# flute.net
KiCad netlist of a schematic drawn in EAGLE
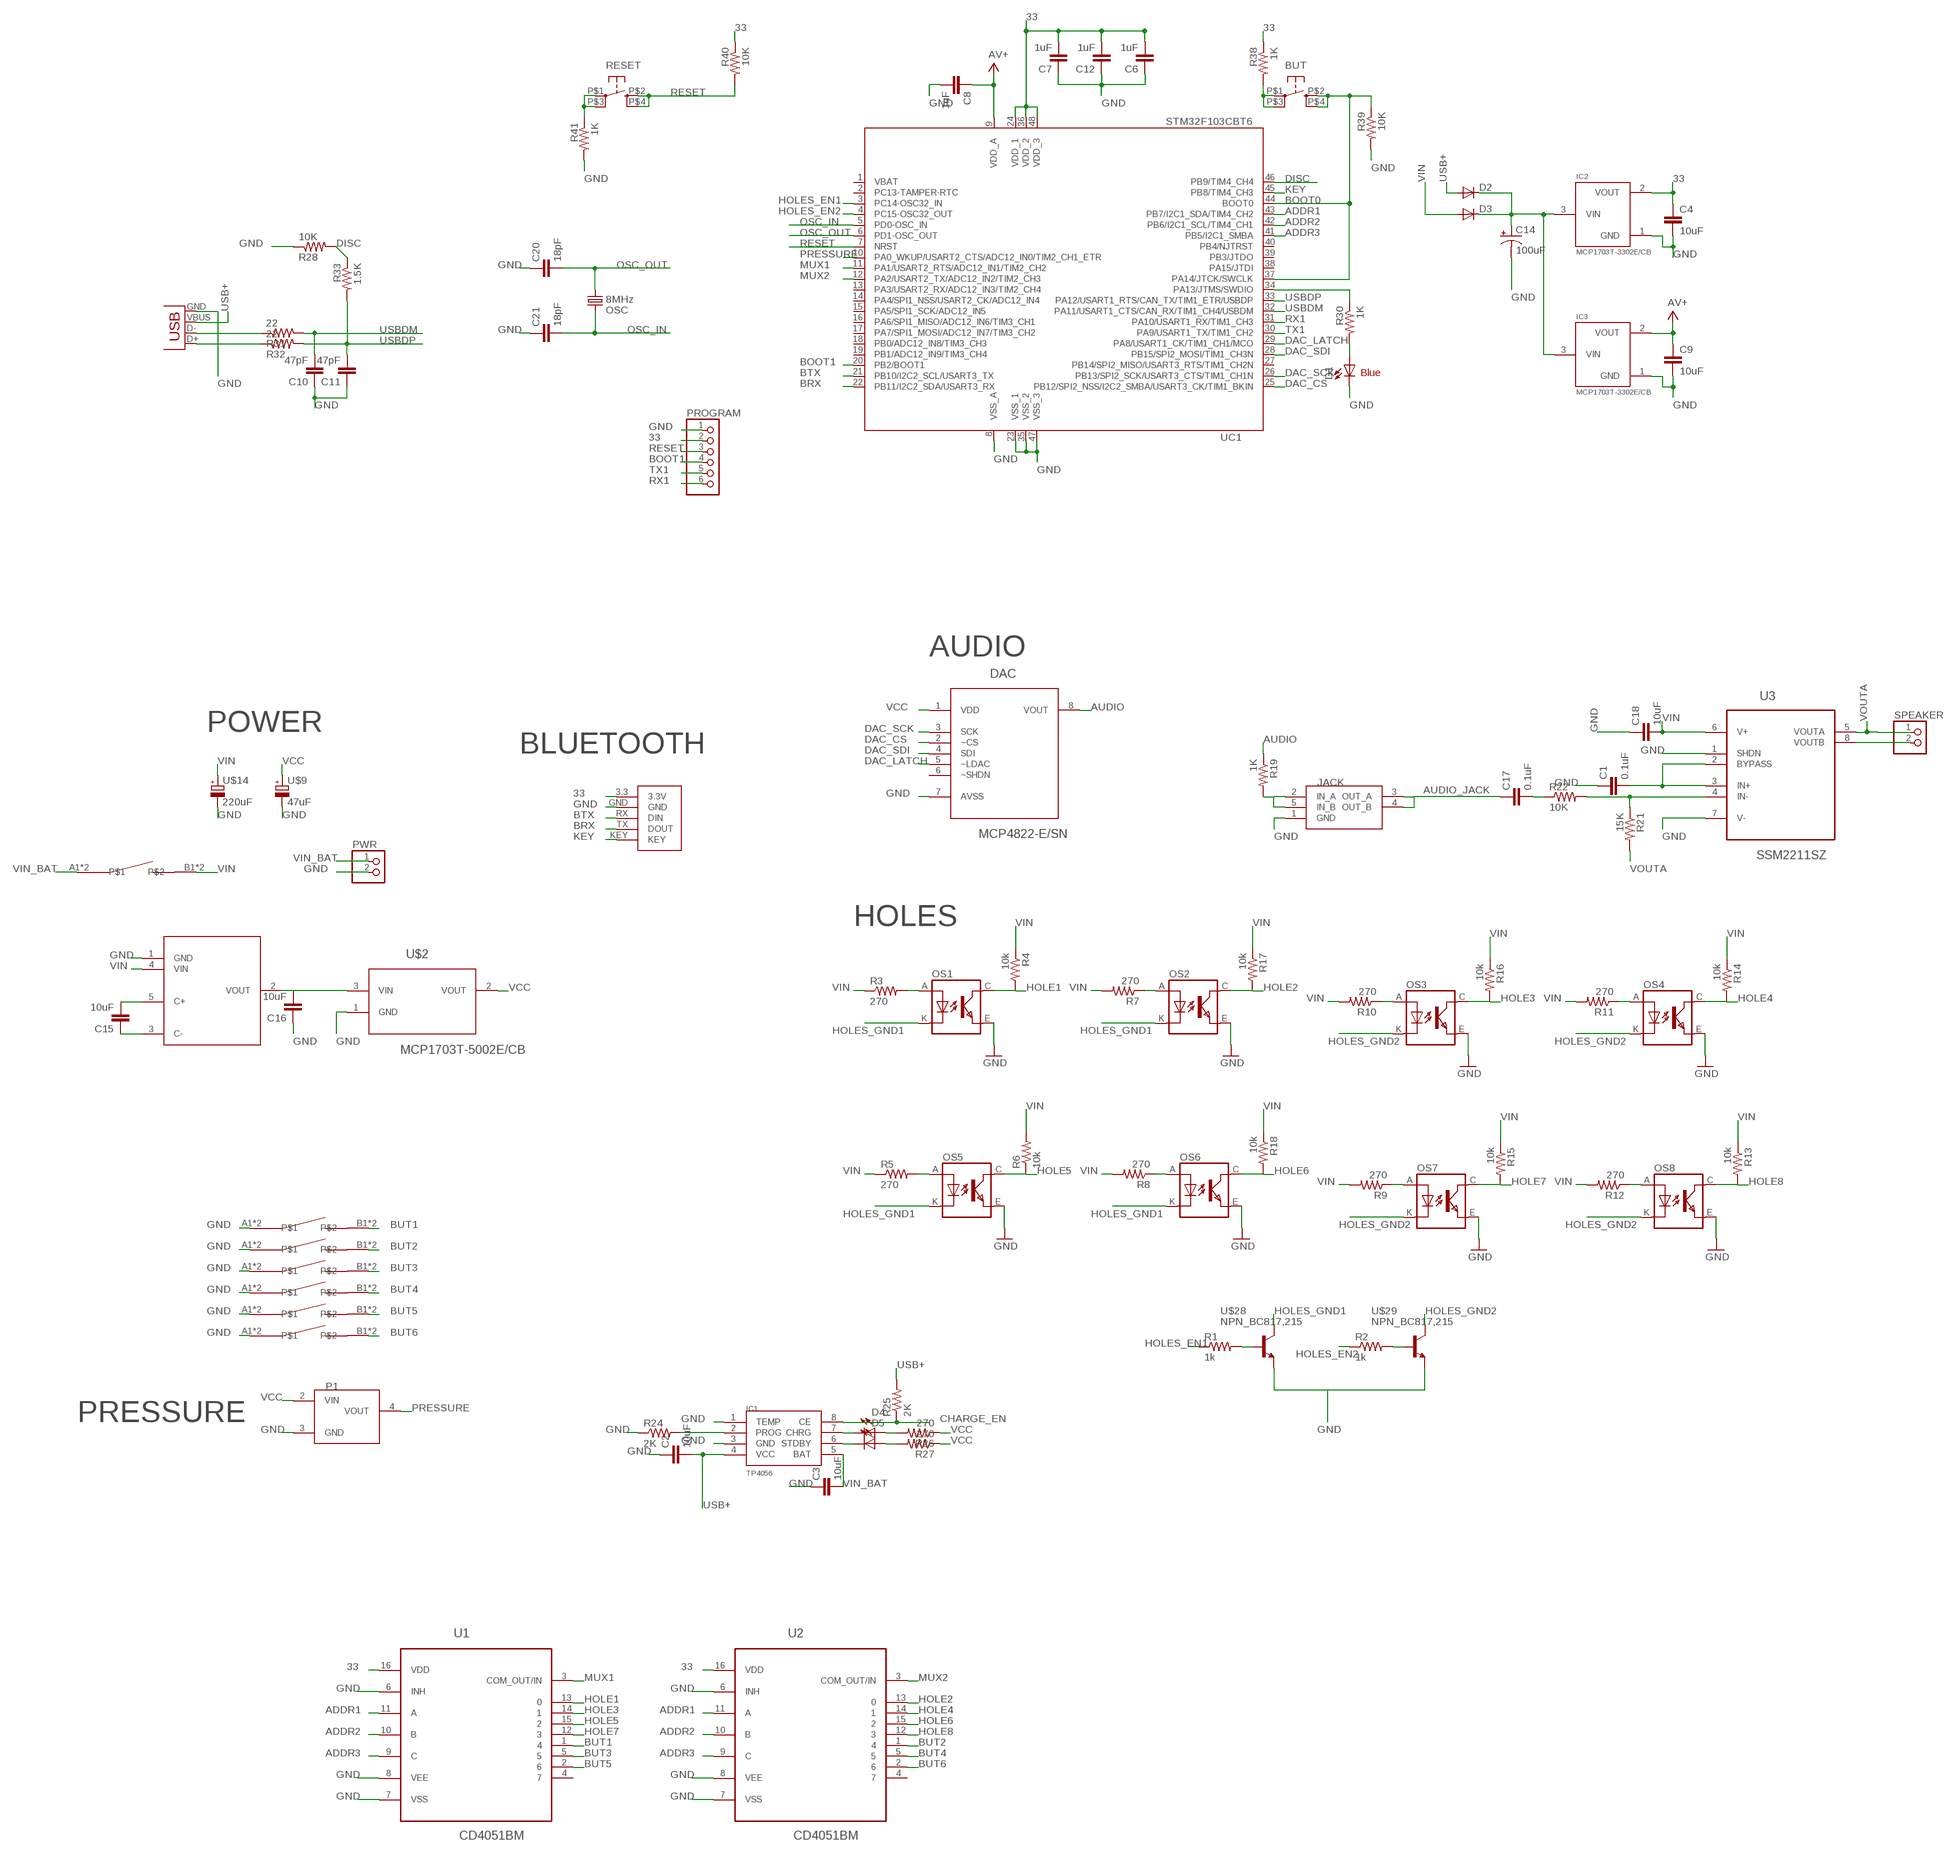
[diagram p0: schematic, sheet 1]

(export (version "E")
  (design (tool "Eeschema 10.0.6"))
  (components
    (comp (ref "BUT")
      (value "KMR211GLFS")
      (footprint "eagle-import:PUSHBUTTON-KMR241GLFS")
      (libsource (lib "eagle-import") (part "BUTTON-KMR241GLFS"))
    )
    (comp (ref "C1")
      (value "0.1uF")
      (footprint "eagle-import:0805")
      (libsource (lib "eagle-import") (part "CAP0805"))
    )
    (comp (ref "C2")
      (value "10uF")
      (footprint "eagle-import:0805")
      (libsource (lib "eagle-import") (part "CAP0805"))
    )
    (comp (ref "C3")
      (value "10uF")
      (footprint "eagle-import:0805")
      (libsource (lib "eagle-import") (part "CAP0805"))
    )
    (comp (ref "C4")
      (value "10uF")
      (footprint "eagle-import:0805")
      (libsource (lib "eagle-import") (part "SparkFun2_CAP0805"))
    )
    (comp (ref "C6")
      (value "1uF")
      (footprint "eagle-import:0805")
      (libsource (lib "eagle-import") (part "CAP0805"))
    )
    (comp (ref "C7")
      (value "1uF")
      (footprint "eagle-import:0805")
      (libsource (lib "eagle-import") (part "CAP0805"))
    )
    (comp (ref "C8")
      (value "1uF")
      (footprint "eagle-import:0805")
      (libsource (lib "eagle-import") (part "CAP0805"))
    )
    (comp (ref "C9")
      (value "10uF")
      (footprint "eagle-import:0805")
      (libsource (lib "eagle-import") (part "SparkFun2_CAP0805"))
    )
    (comp (ref "C10")
      (value "47pF")
      (footprint "eagle-import:0805")
      (libsource (lib "eagle-import") (part "CAP0805"))
    )
    (comp (ref "C11")
      (value "47pF")
      (footprint "eagle-import:0805")
      (libsource (lib "eagle-import") (part "CAP0805"))
    )
    (comp (ref "C12")
      (value "1uF")
      (footprint "eagle-import:0805")
      (libsource (lib "eagle-import") (part "CAP0805"))
    )
    (comp (ref "C14")
      (value "100uF")
      (footprint "eagle-import:EIA3216")
      (libsource (lib "eagle-import") (part "CAP_POL1206"))
    )
    (comp (ref "C15")
      (value "10uF")
      (footprint "eagle-import:0805")
      (libsource (lib "eagle-import") (part "CAP0805"))
    )
    (comp (ref "C16")
      (value "10uF")
      (footprint "eagle-import:0805")
      (libsource (lib "eagle-import") (part "CAP0805"))
    )
    (comp (ref "C17")
      (value "0.1uF")
      (footprint "eagle-import:0805")
      (libsource (lib "eagle-import") (part "CAP0805"))
    )
    (comp (ref "C18")
      (value "10uF")
      (footprint "eagle-import:0805")
      (libsource (lib "eagle-import") (part "CAP0805"))
    )
    (comp (ref "C20")
      (value "18pF")
      (footprint "eagle-import:0805")
      (libsource (lib "eagle-import") (part "CAP0805"))
    )
    (comp (ref "C21")
      (value "18pF")
      (footprint "eagle-import:0805")
      (libsource (lib "eagle-import") (part "CAP0805"))
    )
    (comp (ref "D1")
      (value "Blue")
      (footprint "eagle-import:LED-1206")
      (libsource (lib "eagle-import") (part "LED1206"))
    )
    (comp (ref "D2")
      (value "DIODESOD")
      (footprint "eagle-import:SOD-323")
      (libsource (lib "eagle-import") (part "DIODESOD"))
    )
    (comp (ref "D3")
      (value "DIODESOD")
      (footprint "eagle-import:SOD-323")
      (libsource (lib "eagle-import") (part "DIODESOD"))
    )
    (comp (ref "D4")
      (value "Red")
      (footprint "eagle-import:LED-1206")
      (libsource (lib "eagle-import") (part "LED1206"))
    )
    (comp (ref "D5")
      (value "Green")
      (footprint "eagle-import:LED-1206")
      (libsource (lib "eagle-import") (part "LED1206"))
    )
    (comp (ref "DAC")
      (value "MCP4822-E/SN")
      (footprint "eagle-import:SOIC8-N_MC")
      (libsource (lib "eagle-import") (part "MCP4822-E/SN"))
    )
    (comp (ref "IC1")
      (value "TP4056")
      (footprint "eagle-import:SOP-8")
      (libsource (lib "eagle-import") (part "TP4056"))
    )
    (comp (ref "IC2")
      (value "MCP1703T-3302E/CB")
      (footprint "eagle-import:SOT23")
      (libsource (lib "eagle-import") (part "MCP1700T"))
    )
    (comp (ref "IC3")
      (value "MCP1703T-3302E/CB")
      (footprint "eagle-import:SOT23")
      (libsource (lib "eagle-import") (part "MCP1700T"))
    )
    (comp (ref "JACK")
      (value "JACK")
      (footprint "eagle-import:3F07")
      (libsource (lib "eagle-import") (part "JACK"))
    )
    (comp (ref "OS1")
      (value "TCRT5000")
      (footprint "eagle-import:TCRT5000")
      (libsource (lib "eagle-import") (part "TCRT5000"))
    )
    (comp (ref "OS2")
      (value "TCRT5000")
      (footprint "eagle-import:TCRT5000")
      (libsource (lib "eagle-import") (part "TCRT5000"))
    )
    (comp (ref "OS3")
      (value "TCRT5000")
      (footprint "eagle-import:TCRT5000")
      (libsource (lib "eagle-import") (part "TCRT5000"))
    )
    (comp (ref "OS4")
      (value "TCRT5000")
      (footprint "eagle-import:TCRT5000")
      (libsource (lib "eagle-import") (part "TCRT5000"))
    )
    (comp (ref "OS5")
      (value "TCRT5000")
      (footprint "eagle-import:TCRT5000")
      (libsource (lib "eagle-import") (part "TCRT5000"))
    )
    (comp (ref "OS6")
      (value "TCRT5000")
      (footprint "eagle-import:TCRT5000")
      (libsource (lib "eagle-import") (part "TCRT5000"))
    )
    (comp (ref "OS7")
      (value "TCRT5000")
      (footprint "eagle-import:TCRT5000")
      (libsource (lib "eagle-import") (part "TCRT5000"))
    )
    (comp (ref "OS8")
      (value "TCRT5000")
      (footprint "eagle-import:TCRT5000")
      (libsource (lib "eagle-import") (part "TCRT5000"))
    )
    (comp (ref "OSC")
      (value "8MHz")
      (footprint "eagle-import:CRYSTAL-SMD-5X3")
      (libsource (lib "eagle-import") (part "CRYSTAL5X3"))
    )
    (comp (ref "P1")
      (value "PRESSURE_SENSOR")
      (footprint "eagle-import:MPXV5050GP")
      (libsource (lib "eagle-import") (part "PRESSURE_SENSOR"))
    )
    (comp (ref "PROGRAM")
      (value "CONNEC_1X066PADS")
      (footprint "eagle-import:6PADS")
      (libsource (lib "eagle-import") (part "CONNEC_1X066PADS"))
    )
    (comp (ref "PWR")
      (value "CONNEC_1X02BASIC")
      (footprint "eagle-import:CONNEC_1X02")
      (libsource (lib "eagle-import") (part "CONNEC_1X02BASIC"))
    )
    (comp (ref "R1")
      (value "1k")
      (footprint "eagle-import:0805")
      (libsource (lib "eagle-import") (part "RESISTOR0805-RES"))
    )
    (comp (ref "R2")
      (value "1k")
      (footprint "eagle-import:0805")
      (libsource (lib "eagle-import") (part "RESISTOR0805-RES"))
    )
    (comp (ref "R3")
      (value "270")
      (footprint "eagle-import:0805")
      (libsource (lib "eagle-import") (part "RESISTOR0805-RES"))
    )
    (comp (ref "R4")
      (value "10k")
      (footprint "eagle-import:0805")
      (libsource (lib "eagle-import") (part "RESISTOR0805-RES"))
    )
    (comp (ref "R5")
      (value "270")
      (footprint "eagle-import:0805")
      (libsource (lib "eagle-import") (part "RESISTOR0805-RES"))
    )
    (comp (ref "R6")
      (value "10k")
      (footprint "eagle-import:0805")
      (libsource (lib "eagle-import") (part "RESISTOR0805-RES"))
    )
    (comp (ref "R7")
      (value "270")
      (footprint "eagle-import:0805")
      (libsource (lib "eagle-import") (part "RESISTOR0805-RES"))
    )
    (comp (ref "R8")
      (value "270")
      (footprint "eagle-import:0805")
      (libsource (lib "eagle-import") (part "RESISTOR0805-RES"))
    )
    (comp (ref "R9")
      (value "270")
      (footprint "eagle-import:0805")
      (libsource (lib "eagle-import") (part "RESISTOR0805-RES"))
    )
    (comp (ref "R10")
      (value "270")
      (footprint "eagle-import:0805")
      (libsource (lib "eagle-import") (part "RESISTOR0805-RES"))
    )
    (comp (ref "R11")
      (value "270")
      (footprint "eagle-import:0805")
      (libsource (lib "eagle-import") (part "RESISTOR0805-RES"))
    )
    (comp (ref "R12")
      (value "270")
      (footprint "eagle-import:0805")
      (libsource (lib "eagle-import") (part "RESISTOR0805-RES"))
    )
    (comp (ref "R13")
      (value "10k")
      (footprint "eagle-import:0805")
      (libsource (lib "eagle-import") (part "RESISTOR0805-RES"))
    )
    (comp (ref "R14")
      (value "10k")
      (footprint "eagle-import:0805")
      (libsource (lib "eagle-import") (part "RESISTOR0805-RES"))
    )
    (comp (ref "R15")
      (value "10k")
      (footprint "eagle-import:0805")
      (libsource (lib "eagle-import") (part "RESISTOR0805-RES"))
    )
    (comp (ref "R16")
      (value "10k")
      (footprint "eagle-import:0805")
      (libsource (lib "eagle-import") (part "RESISTOR0805-RES"))
    )
    (comp (ref "R17")
      (value "10k")
      (footprint "eagle-import:0805")
      (libsource (lib "eagle-import") (part "RESISTOR0805-RES"))
    )
    (comp (ref "R18")
      (value "10k")
      (footprint "eagle-import:0805")
      (libsource (lib "eagle-import") (part "RESISTOR0805-RES"))
    )
    (comp (ref "R19")
      (value "1K")
      (footprint "eagle-import:0805")
      (libsource (lib "eagle-import") (part "RESISTOR0805-RES"))
    )
    (comp (ref "R21")
      (value "15K")
      (footprint "eagle-import:0805")
      (libsource (lib "eagle-import") (part "RESISTOR0805-RES"))
    )
    (comp (ref "R22")
      (value "10K")
      (footprint "eagle-import:0805")
      (libsource (lib "eagle-import") (part "RESISTOR0805-RES"))
    )
    (comp (ref "R24")
      (value "2K")
      (footprint "eagle-import:0805")
      (libsource (lib "eagle-import") (part "RESISTOR0805-RES"))
    )
    (comp (ref "R25")
      (value "2K")
      (footprint "eagle-import:0805")
      (libsource (lib "eagle-import") (part "RESISTOR0805-RES"))
    )
    (comp (ref "R26")
      (value "270")
      (footprint "eagle-import:0805")
      (libsource (lib "eagle-import") (part "RESISTOR0805-RES"))
    )
    (comp (ref "R27")
      (value "270")
      (footprint "eagle-import:0805")
      (libsource (lib "eagle-import") (part "RESISTOR0805-RES"))
    )
    (comp (ref "R28")
      (value "10K")
      (footprint "eagle-import:0805")
      (libsource (lib "eagle-import") (part "RESISTOR0805-RES"))
    )
    (comp (ref "R30")
      (value "1K")
      (footprint "eagle-import:0805")
      (libsource (lib "eagle-import") (part "RESISTOR0805-RES"))
    )
    (comp (ref "R31")
      (value "22")
      (footprint "eagle-import:0805")
      (libsource (lib "eagle-import") (part "RESISTOR0805-RES"))
    )
    (comp (ref "R32")
      (value "22")
      (footprint "eagle-import:0805")
      (libsource (lib "eagle-import") (part "RESISTOR0805-RES"))
    )
    (comp (ref "R33")
      (value "1.5K")
      (footprint "eagle-import:0805")
      (libsource (lib "eagle-import") (part "RESISTOR0805-RES"))
    )
    (comp (ref "R38")
      (value "1K")
      (footprint "eagle-import:0805")
      (libsource (lib "eagle-import") (part "RESISTOR0805-RES"))
    )
    (comp (ref "R39")
      (value "10K")
      (footprint "eagle-import:0805")
      (libsource (lib "eagle-import") (part "RESISTOR0805-RES"))
    )
    (comp (ref "R40")
      (value "10K")
      (footprint "eagle-import:0805")
      (libsource (lib "eagle-import") (part "RESISTOR0805-RES"))
    )
    (comp (ref "R41")
      (value "1K")
      (footprint "eagle-import:0805")
      (libsource (lib "eagle-import") (part "RESISTOR0805-RES"))
    )
    (comp (ref "RESET")
      (value "KMR211GLFS")
      (footprint "eagle-import:PUSHBUTTON-KMR241GLFS")
      (libsource (lib "eagle-import") (part "BUTTON-KMR241GLFS"))
    )
    (comp (ref "SPEAKER")
      (value "CONNEC_1X02BASIC")
      (footprint "eagle-import:CONNEC_1X02")
      (libsource (lib "eagle-import") (part "CONNEC_1X02BASIC"))
    )
    (comp (ref "U$1")
      (value "MAX1683")
      (footprint "eagle-import:SOT23-5")
      (libsource (lib "eagle-import") (part "MAX1683"))
    )
    (comp (ref "U$2")
      (value "MCP1703T-5002E/CB")
      (footprint "eagle-import:SOT95P300X145-3N")
      (libsource (lib "eagle-import") (part "MCP1703T-5002E/CB"))
    )
    (comp (ref "U$9")
      (value "47uF")
      (footprint "eagle-import:PANASONIC_D")
      (libsource (lib "eagle-import") (part "CPOL_EUPANASONIC_D"))
    )
    (comp (ref "U$14")
      (value "220uF")
      (footprint "eagle-import:PANASONIC_D8")
      (libsource (lib "eagle-import") (part "CPOL_EUPANASONIC_D8"))
    )
    (comp (ref "U$16")
      (value "SWITCHKCD11")
      (footprint "eagle-import:KCD11")
      (libsource (lib "eagle-import") (part "SWITCHKCD11"))
    )
    (comp (ref "U$18")
      (value "SWITCH6X6X10")
      (footprint "eagle-import:SWITCH_6X6X10")
      (libsource (lib "eagle-import") (part "SWITCH6X6X10"))
    )
    (comp (ref "U$19")
      (value "SWITCH6X6X10")
      (footprint "eagle-import:SWITCH_6X6X10")
      (libsource (lib "eagle-import") (part "SWITCH6X6X10"))
    )
    (comp (ref "U$20")
      (value "SWITCH6X6X10")
      (footprint "eagle-import:SWITCH_6X6X10")
      (libsource (lib "eagle-import") (part "SWITCH6X6X10"))
    )
    (comp (ref "U$21")
      (value "SWITCH6X6X10")
      (footprint "eagle-import:SWITCH_6X6X10")
      (libsource (lib "eagle-import") (part "SWITCH6X6X10"))
    )
    (comp (ref "U$22")
      (value "SWITCH6X6X10")
      (footprint "eagle-import:SWITCH_6X6X10")
      (libsource (lib "eagle-import") (part "SWITCH6X6X10"))
    )
    (comp (ref "U$23")
      (value "SWITCH6X6X10")
      (footprint "eagle-import:SWITCH_6X6X10")
      (libsource (lib "eagle-import") (part "SWITCH6X6X10"))
    )
    (comp (ref "U$24")
      (value "HC05")
      (footprint "eagle-import:HC-05")
      (libsource (lib "eagle-import") (part "HC05"))
    )
    (comp (ref "U$28")
      (value "NPN_BC817,215")
      (footprint "eagle-import:SOT-23")
      (libsource (lib "eagle-import") (part "NPN_BC817,215"))
    )
    (comp (ref "U$29")
      (value "NPN_BC817,215")
      (footprint "eagle-import:SOT-23")
      (libsource (lib "eagle-import") (part "NPN_BC817,215"))
    )
    (comp (ref "U1")
      (value "CD4051BM")
      (footprint "eagle-import:SOIC127P600X175-16N")
      (libsource (lib "eagle-import") (part "CD4051BM"))
    )
    (comp (ref "U2")
      (value "CD4051BM")
      (footprint "eagle-import:SOIC127P600X175-16N")
      (libsource (lib "eagle-import") (part "CD4051BM"))
    )
    (comp (ref "U3")
      (value "SSM2211SZ")
      (footprint "eagle-import:SOIC127P600X175-8N")
      (libsource (lib "eagle-import") (part "SSM2211SZ"))
    )
    (comp (ref "UC1")
      (value "STM32F103CBT6")
      (footprint "eagle-import:LQFP48")
      (libsource (lib "eagle-import") (part "STM32F103CB"))
    )
    (comp (ref "X1")
      (value "USB-MINIB")
      (footprint "eagle-import:USB-MINIB")
      (libsource (lib "eagle-import") (part "USBSMD"))
    )
  )
  (nets
    (net (code "1") (name "/33") (class "Default")
      (node (ref "C12") (pin "2") (pinfunction "2_2") (pintype "passive"))
      (node (ref "C4") (pin "1") (pinfunction "1_1") (pintype "passive"))
      (node (ref "C6") (pin "2") (pinfunction "2_2") (pintype "passive"))
      (node (ref "C7") (pin "2") (pinfunction "2_2") (pintype "passive"))
      (node (ref "IC2") (pin "2") (pinfunction "VOUT_2") (pintype "bidirectional"))
      (node (ref "PROGRAM") (pin "2") (pinfunction "2_2") (pintype "passive"))
      (node (ref "R38") (pin "1") (pinfunction "1_1") (pintype "passive"))
      (node (ref "R40") (pin "1") (pinfunction "1_1") (pintype "passive"))
      (node (ref "U$24") (pin "3.3") (pinfunction "3.3V_3.3") (pintype "bidirectional"))
      (node (ref "U1") (pin "16") (pinfunction "VDD_16") (pintype "input"))
      (node (ref "U2") (pin "16") (pinfunction "VDD_16") (pintype "input"))
      (node (ref "UC1") (pin "24") (pinfunction "VDD_1_24") (pintype "power_in"))
      (node (ref "UC1") (pin "36") (pinfunction "VDD_2_36") (pintype "power_in"))
      (node (ref "UC1") (pin "48") (pinfunction "VDD_3_48") (pintype "power_in"))
    )
    (net (code "2") (name "/ADDR1") (class "Default")
      (node (ref "U1") (pin "11") (pinfunction "A_11") (pintype "input"))
      (node (ref "U2") (pin "11") (pinfunction "A_11") (pintype "input"))
      (node (ref "UC1") (pin "43") (pinfunction "PB7/I2C1_SDA/TIM4_CH2_43") (pintype "bidirectional"))
    )
    (net (code "3") (name "/ADDR2") (class "Default")
      (node (ref "U1") (pin "10") (pinfunction "B_10") (pintype "input"))
      (node (ref "U2") (pin "10") (pinfunction "B_10") (pintype "input"))
      (node (ref "UC1") (pin "42") (pinfunction "PB6/I2C1_SCL/TIM4_CH1_42") (pintype "input"))
    )
    (net (code "4") (name "/ADDR3") (class "Default")
      (node (ref "U1") (pin "9") (pinfunction "C_9") (pintype "bidirectional"))
      (node (ref "U2") (pin "9") (pinfunction "C_9") (pintype "bidirectional"))
      (node (ref "UC1") (pin "41") (pinfunction "PB5/I2C1_SMBA_41") (pintype "input"))
    )
    (net (code "5") (name "/AUDIO") (class "Default")
      (node (ref "DAC") (pin "8") (pinfunction "VOUT_8") (pintype "output"))
      (node (ref "R19") (pin "1") (pinfunction "1_1") (pintype "passive"))
    )
    (net (code "6") (name "/AUDIO_JACK") (class "Default")
      (node (ref "C17") (pin "1") (pinfunction "1_1") (pintype "passive"))
      (node (ref "JACK") (pin "3") (pinfunction "OUT_A_3") (pintype "bidirectional"))
      (node (ref "JACK") (pin "4") (pinfunction "OUT_B_4") (pintype "bidirectional"))
    )
    (net (code "7") (name "/BOOT1") (class "Default")
      (node (ref "PROGRAM") (pin "4") (pinfunction "4_4") (pintype "passive"))
      (node (ref "UC1") (pin "20") (pinfunction "PB2/BOOT1_20") (pintype "bidirectional"))
    )
    (net (code "8") (name "/BRX") (class "Default")
      (node (ref "U$24") (pin "TX") (pinfunction "DOUT_TX") (pintype "bidirectional"))
      (node (ref "UC1") (pin "22") (pinfunction "PB11/I2C2_SDA/USART3_RX_22") (pintype "input"))
    )
    (net (code "9") (name "/BTX") (class "Default")
      (node (ref "U$24") (pin "RX") (pinfunction "DIN_RX") (pintype "bidirectional"))
      (node (ref "UC1") (pin "21") (pinfunction "PB10/I2C2_SCL/USART3_TX_21") (pintype "input"))
    )
    (net (code "10") (name "/BUT1") (class "Default")
      (node (ref "U$18") (pin "B1") (pinfunction "P$2_B1") (pintype "bidirectional"))
      (node (ref "U$18") (pin "B2") (pinfunction "P$2_B2") (pintype "bidirectional"))
      (node (ref "U1") (pin "1") (pinfunction "4_1") (pintype "bidirectional"))
    )
    (net (code "11") (name "/BUT2") (class "Default")
      (node (ref "U$19") (pin "B1") (pinfunction "P$2_B1") (pintype "bidirectional"))
      (node (ref "U$19") (pin "B2") (pinfunction "P$2_B2") (pintype "bidirectional"))
      (node (ref "U2") (pin "1") (pinfunction "4_1") (pintype "bidirectional"))
    )
    (net (code "12") (name "/BUT3") (class "Default")
      (node (ref "U$20") (pin "B1") (pinfunction "P$2_B1") (pintype "bidirectional"))
      (node (ref "U$20") (pin "B2") (pinfunction "P$2_B2") (pintype "bidirectional"))
      (node (ref "U1") (pin "5") (pinfunction "5_5") (pintype "bidirectional"))
    )
    (net (code "13") (name "/BUT4") (class "Default")
      (node (ref "U$21") (pin "B1") (pinfunction "P$2_B1") (pintype "bidirectional"))
      (node (ref "U$21") (pin "B2") (pinfunction "P$2_B2") (pintype "bidirectional"))
      (node (ref "U2") (pin "5") (pinfunction "5_5") (pintype "bidirectional"))
    )
    (net (code "14") (name "/BUT5") (class "Default")
      (node (ref "U$22") (pin "B1") (pinfunction "P$2_B1") (pintype "bidirectional"))
      (node (ref "U$22") (pin "B2") (pinfunction "P$2_B2") (pintype "bidirectional"))
      (node (ref "U1") (pin "2") (pinfunction "6_2") (pintype "bidirectional"))
    )
    (net (code "15") (name "/BUT6") (class "Default")
      (node (ref "U$23") (pin "B1") (pinfunction "P$2_B1") (pintype "bidirectional"))
      (node (ref "U$23") (pin "B2") (pinfunction "P$2_B2") (pintype "bidirectional"))
      (node (ref "U2") (pin "2") (pinfunction "6_2") (pintype "bidirectional"))
    )
    (net (code "16") (name "/CHARGE_EN") (class "Default")
      (node (ref "IC1") (pin "8") (pinfunction "CE_8") (pintype "bidirectional"))
      (node (ref "R25") (pin "1") (pinfunction "1_1") (pintype "passive"))
    )
    (net (code "17") (name "/DAC_CS") (class "Default")
      (node (ref "DAC") (pin "2") (pinfunction "~{CS}_2") (pintype "input"))
      (node (ref "UC1") (pin "25") (pinfunction "PB12/SPI2_NSS/I2C2_SMBA/USART3_CK/TIM1_BKIN_25") (pintype "input"))
    )
    (net (code "18") (name "/DAC_LATCH") (class "Default")
      (node (ref "DAC") (pin "5") (pinfunction "~{LDAC}_5") (pintype "input"))
      (node (ref "UC1") (pin "29") (pinfunction "PA8/USART1_CK/TIM1_CH1/MCO_29") (pintype "bidirectional"))
    )
    (net (code "19") (name "/DAC_SCK") (class "Default")
      (node (ref "DAC") (pin "3") (pinfunction "SCK_3") (pintype "input"))
      (node (ref "UC1") (pin "26") (pinfunction "PB13/SPI2_SCK/USART3_CTS/TIM1_CH1N_26") (pintype "input"))
    )
    (net (code "20") (name "/DAC_SDI") (class "Default")
      (node (ref "DAC") (pin "4") (pinfunction "SDI_4") (pintype "input"))
      (node (ref "UC1") (pin "28") (pinfunction "PB15/SPI2_MOSI/TIM1_CH3N_28") (pintype "input"))
    )
    (net (code "21") (name "/DISC") (class "Default")
      (node (ref "R28") (pin "2") (pinfunction "2_2") (pintype "passive"))
      (node (ref "R33") (pin "1") (pinfunction "1_1") (pintype "passive"))
      (node (ref "UC1") (pin "46") (pinfunction "PB9/TIM4_CH4_46") (pintype "input"))
    )
    (net (code "22") (name "/HOLE1") (class "Default")
      (node (ref "OS1") (pin "C") (pinfunction "COLLECTOR_C") (pintype "passive"))
      (node (ref "R4") (pin "2") (pinfunction "2_2") (pintype "passive"))
      (node (ref "U1") (pin "13") (pinfunction "0_13") (pintype "bidirectional"))
    )
    (net (code "23") (name "/HOLE2") (class "Default")
      (node (ref "OS2") (pin "C") (pinfunction "COLLECTOR_C") (pintype "passive"))
      (node (ref "R17") (pin "2") (pinfunction "2_2") (pintype "passive"))
      (node (ref "U2") (pin "13") (pinfunction "0_13") (pintype "bidirectional"))
    )
    (net (code "24") (name "/HOLE3") (class "Default")
      (node (ref "OS3") (pin "C") (pinfunction "COLLECTOR_C") (pintype "passive"))
      (node (ref "R16") (pin "2") (pinfunction "2_2") (pintype "passive"))
      (node (ref "U1") (pin "14") (pinfunction "1_14") (pintype "bidirectional"))
    )
    (net (code "25") (name "/HOLE4") (class "Default")
      (node (ref "OS4") (pin "C") (pinfunction "COLLECTOR_C") (pintype "passive"))
      (node (ref "R14") (pin "2") (pinfunction "2_2") (pintype "passive"))
      (node (ref "U2") (pin "14") (pinfunction "1_14") (pintype "bidirectional"))
    )
    (net (code "26") (name "/HOLE5") (class "Default")
      (node (ref "OS5") (pin "C") (pinfunction "COLLECTOR_C") (pintype "passive"))
      (node (ref "R6") (pin "1") (pinfunction "1_1") (pintype "passive"))
      (node (ref "U1") (pin "15") (pinfunction "2_15") (pintype "bidirectional"))
    )
    (net (code "27") (name "/HOLE6") (class "Default")
      (node (ref "OS6") (pin "C") (pinfunction "COLLECTOR_C") (pintype "passive"))
      (node (ref "R18") (pin "2") (pinfunction "2_2") (pintype "passive"))
      (node (ref "U2") (pin "15") (pinfunction "2_15") (pintype "bidirectional"))
    )
    (net (code "28") (name "/HOLE7") (class "Default")
      (node (ref "OS7") (pin "C") (pinfunction "COLLECTOR_C") (pintype "passive"))
      (node (ref "R15") (pin "2") (pinfunction "2_2") (pintype "passive"))
      (node (ref "U1") (pin "12") (pinfunction "3_12") (pintype "bidirectional"))
    )
    (net (code "29") (name "/HOLE8") (class "Default")
      (node (ref "OS8") (pin "C") (pinfunction "COLLECTOR_C") (pintype "passive"))
      (node (ref "R13") (pin "2") (pinfunction "2_2") (pintype "passive"))
      (node (ref "U2") (pin "12") (pinfunction "3_12") (pintype "bidirectional"))
    )
    (net (code "30") (name "/HOLES_EN1") (class "Default")
      (node (ref "R1") (pin "1") (pinfunction "1_1") (pintype "passive"))
      (node (ref "UC1") (pin "3") (pinfunction "PC14-OSC32_IN_3") (pintype "input"))
    )
    (net (code "31") (name "/HOLES_EN2") (class "Default")
      (node (ref "R2") (pin "1") (pinfunction "1_1") (pintype "passive"))
      (node (ref "UC1") (pin "4") (pinfunction "PC15-OSC32_OUT_4") (pintype "input"))
    )
    (net (code "32") (name "/HOLES_GND1") (class "Default")
      (node (ref "OS1") (pin "K") (pinfunction "CATHODE_K") (pintype "passive"))
      (node (ref "OS2") (pin "K") (pinfunction "CATHODE_K") (pintype "passive"))
      (node (ref "OS5") (pin "K") (pinfunction "CATHODE_K") (pintype "passive"))
      (node (ref "OS6") (pin "K") (pinfunction "CATHODE_K") (pintype "passive"))
      (node (ref "U$28") (pin "3") (pinfunction "C_3") (pintype "passive"))
    )
    (net (code "33") (name "/HOLES_GND2") (class "Default")
      (node (ref "OS3") (pin "K") (pinfunction "CATHODE_K") (pintype "passive"))
      (node (ref "OS4") (pin "K") (pinfunction "CATHODE_K") (pintype "passive"))
      (node (ref "OS7") (pin "K") (pinfunction "CATHODE_K") (pintype "passive"))
      (node (ref "OS8") (pin "K") (pinfunction "CATHODE_K") (pintype "passive"))
      (node (ref "U$29") (pin "3") (pinfunction "C_3") (pintype "passive"))
    )
    (net (code "34") (name "/KEY") (class "Default")
      (node (ref "U$24") (pin "KEY") (pinfunction "KEY_KEY") (pintype "bidirectional"))
      (node (ref "UC1") (pin "45") (pinfunction "PB8/TIM4_CH3_45") (pintype "bidirectional"))
    )
    (net (code "35") (name "/MUX1") (class "Default")
      (node (ref "U1") (pin "3") (pinfunction "COM_OUT/IN_3") (pintype "bidirectional"))
      (node (ref "UC1") (pin "11") (pinfunction "PA1/USART2_RTS/ADC12_IN1/TIM2_CH2_11") (pintype "bidirectional"))
    )
    (net (code "36") (name "/MUX2") (class "Default")
      (node (ref "U2") (pin "3") (pinfunction "COM_OUT/IN_3") (pintype "bidirectional"))
      (node (ref "UC1") (pin "12") (pinfunction "PA2/USART2_TX/ADC12_IN2/TIM2_CH3_12") (pintype "bidirectional"))
    )
    (net (code "37") (name "/OSC_IN") (class "Default")
      (node (ref "C21") (pin "2") (pinfunction "2_2") (pintype "passive"))
      (node (ref "OSC") (pin "3") (pinfunction "2_3") (pintype "passive"))
      (node (ref "UC1") (pin "5") (pinfunction "PD0-OSC_IN_5") (pintype "input"))
    )
    (net (code "38") (name "/OSC_OUT") (class "Default")
      (node (ref "C20") (pin "2") (pinfunction "2_2") (pintype "passive"))
      (node (ref "OSC") (pin "1") (pinfunction "1_1") (pintype "passive"))
      (node (ref "UC1") (pin "6") (pinfunction "PD1-OSC_OUT_6") (pintype "input"))
    )
    (net (code "39") (name "/PRESSURE") (class "Default")
      (node (ref "P1") (pin "4") (pinfunction "VOUT_4") (pintype "bidirectional"))
      (node (ref "UC1") (pin "10") (pinfunction "PA0_WKUP/USART2_CTS/ADC12_IN0/TIM2_CH1_ETR_10") (pintype "bidirectional"))
    )
    (net (code "40") (name "/RESET") (class "Default")
      (node (ref "PROGRAM") (pin "3") (pinfunction "3_3") (pintype "passive"))
      (node (ref "R40") (pin "2") (pinfunction "2_2") (pintype "passive"))
      (node (ref "RESET") (pin "P$2") (pinfunction "2_P$2") (pintype "passive"))
      (node (ref "RESET") (pin "P$4") (pinfunction "4_P$4") (pintype "passive"))
      (node (ref "UC1") (pin "7") (pinfunction "NRST_7") (pintype "input"))
    )
    (net (code "41") (name "/RX1") (class "Default")
      (node (ref "PROGRAM") (pin "6") (pinfunction "6_6") (pintype "passive"))
      (node (ref "UC1") (pin "31") (pinfunction "PA10/USART1_RX/TIM1_CH3_31") (pintype "bidirectional"))
    )
    (net (code "42") (name "/TX1") (class "Default")
      (node (ref "PROGRAM") (pin "5") (pinfunction "5_5") (pintype "passive"))
      (node (ref "UC1") (pin "30") (pinfunction "PA9/USART1_TX/TIM1_CH2_30") (pintype "input"))
    )
    (net (code "43") (name "/USB+") (class "Default")
      (node (ref "C2") (pin "2") (pinfunction "2_2") (pintype "passive"))
      (node (ref "D2") (pin "2") (pinfunction "A_2") (pintype "passive"))
      (node (ref "IC1") (pin "4") (pinfunction "VCC_4") (pintype "bidirectional"))
      (node (ref "R25") (pin "2") (pinfunction "2_2") (pintype "passive"))
      (node (ref "X1") (pin "VBUS") (pinfunction "VBUS_VBUS") (pintype "bidirectional"))
    )
    (net (code "44") (name "/USBDM") (class "Default")
      (node (ref "C10") (pin "2") (pinfunction "2_2") (pintype "passive"))
      (node (ref "R31") (pin "2") (pinfunction "2_2") (pintype "passive"))
      (node (ref "UC1") (pin "32") (pinfunction "PA11/USART1_CTS/CAN_RX/TIM1_CH4/USBDM_32") (pintype "bidirectional"))
    )
    (net (code "45") (name "/USBDP") (class "Default")
      (node (ref "C11") (pin "2") (pinfunction "2_2") (pintype "passive"))
      (node (ref "R32") (pin "2") (pinfunction "2_2") (pintype "passive"))
      (node (ref "R33") (pin "2") (pinfunction "2_2") (pintype "passive"))
      (node (ref "UC1") (pin "33") (pinfunction "PA12/USART1_RTS/CAN_TX/TIM1_ETR/USBDP_33") (pintype "bidirectional"))
    )
    (net (code "46") (name "/VBAT") (class "Default")
      (node (ref "UC1") (pin "1") (pinfunction "VBAT_1") (pintype "power_in"))
    )
    (net (code "47") (name "/VCC") (class "Default")
      (node (ref "DAC") (pin "1") (pinfunction "VDD_1") (pintype "power_in"))
      (node (ref "P1") (pin "2") (pinfunction "VIN_2") (pintype "bidirectional"))
      (node (ref "R26") (pin "1") (pinfunction "1_1") (pintype "passive"))
      (node (ref "R27") (pin "1") (pinfunction "1_1") (pintype "passive"))
      (node (ref "U$2") (pin "2") (pinfunction "VOUT_2") (pintype "output"))
      (node (ref "U$9") (pin "+") (pinfunction "+_+") (pintype "passive"))
    )
    (net (code "48") (name "/VIN") (class "Default")
      (node (ref "C18") (pin "2") (pinfunction "2_2") (pintype "passive"))
      (node (ref "D3") (pin "2") (pinfunction "A_2") (pintype "passive"))
      (node (ref "R10") (pin "2") (pinfunction "2_2") (pintype "passive"))
      (node (ref "R11") (pin "2") (pinfunction "2_2") (pintype "passive"))
      (node (ref "R12") (pin "2") (pinfunction "2_2") (pintype "passive"))
      (node (ref "R13") (pin "1") (pinfunction "1_1") (pintype "passive"))
      (node (ref "R14") (pin "1") (pinfunction "1_1") (pintype "passive"))
      (node (ref "R15") (pin "1") (pinfunction "1_1") (pintype "passive"))
      (node (ref "R16") (pin "1") (pinfunction "1_1") (pintype "passive"))
      (node (ref "R17") (pin "1") (pinfunction "1_1") (pintype "passive"))
      (node (ref "R18") (pin "1") (pinfunction "1_1") (pintype "passive"))
      (node (ref "R3") (pin "1") (pinfunction "1_1") (pintype "passive"))
      (node (ref "R4") (pin "1") (pinfunction "1_1") (pintype "passive"))
      (node (ref "R5") (pin "1") (pinfunction "1_1") (pintype "passive"))
      (node (ref "R6") (pin "2") (pinfunction "2_2") (pintype "passive"))
      (node (ref "R7") (pin "2") (pinfunction "2_2") (pintype "passive"))
      (node (ref "R8") (pin "2") (pinfunction "2_2") (pintype "passive"))
      (node (ref "R9") (pin "2") (pinfunction "2_2") (pintype "passive"))
      (node (ref "U$1") (pin "4") (pinfunction "VIN_4") (pintype "bidirectional"))
      (node (ref "U$14") (pin "+") (pinfunction "+_+") (pintype "passive"))
      (node (ref "U$16") (pin "B1") (pinfunction "P$2_B1") (pintype "bidirectional"))
      (node (ref "U$16") (pin "B2") (pinfunction "P$2_B2") (pintype "bidirectional"))
      (node (ref "U3") (pin "6") (pinfunction "V+_6") (pintype "power_in"))
    )
    (net (code "49") (name "/VIN_BAT") (class "Default")
      (node (ref "C3") (pin "2") (pinfunction "2_2") (pintype "passive"))
      (node (ref "IC1") (pin "5") (pinfunction "BAT_5") (pintype "bidirectional"))
      (node (ref "PWR") (pin "1") (pinfunction "1_1") (pintype "passive"))
      (node (ref "U$16") (pin "A1") (pinfunction "P$1_A1") (pintype "bidirectional"))
      (node (ref "U$16") (pin "A2") (pinfunction "P$1_A2") (pintype "bidirectional"))
    )
    (net (code "50") (name "/VOUTA") (class "Default")
      (node (ref "R21") (pin "2") (pinfunction "2_2") (pintype "passive"))
      (node (ref "SPEAKER") (pin "1") (pinfunction "1_1") (pintype "passive"))
      (node (ref "U3") (pin "5") (pinfunction "VOUTA_5") (pintype "output"))
    )
    (net (code "51") (name "AV+") (class "Default")
      (node (ref "C8") (pin "1") (pinfunction "1_1") (pintype "passive"))
      (node (ref "C9") (pin "1") (pinfunction "1_1") (pintype "passive"))
      (node (ref "IC3") (pin "2") (pinfunction "VOUT_2") (pintype "bidirectional"))
      (node (ref "UC1") (pin "9") (pinfunction "VDD_A_9") (pintype "power_in"))
    )
    (net (code "52") (name "GND") (class "Default")
      (node (ref "C1") (pin "1") (pinfunction "1_1") (pintype "passive"))
      (node (ref "C10") (pin "1") (pinfunction "1_1") (pintype "passive"))
      (node (ref "C11") (pin "1") (pinfunction "1_1") (pintype "passive"))
      (node (ref "C12") (pin "1") (pinfunction "1_1") (pintype "passive"))
      (node (ref "C14") (pin "C") (pinfunction "-_C") (pintype "passive"))
      (node (ref "C16") (pin "1") (pinfunction "1_1") (pintype "passive"))
      (node (ref "C18") (pin "1") (pinfunction "1_1") (pintype "passive"))
      (node (ref "C2") (pin "1") (pinfunction "1_1") (pintype "passive"))
      (node (ref "C20") (pin "1") (pinfunction "1_1") (pintype "passive"))
      (node (ref "C21") (pin "1") (pinfunction "1_1") (pintype "passive"))
      (node (ref "C3") (pin "1") (pinfunction "1_1") (pintype "passive"))
      (node (ref "C4") (pin "2") (pinfunction "2_2") (pintype "passive"))
      (node (ref "C6") (pin "1") (pinfunction "1_1") (pintype "passive"))
      (node (ref "C7") (pin "1") (pinfunction "1_1") (pintype "passive"))
      (node (ref "C8") (pin "2") (pinfunction "2_2") (pintype "passive"))
      (node (ref "C9") (pin "2") (pinfunction "2_2") (pintype "passive"))
      (node (ref "D1") (pin "C") (pinfunction "C_C") (pintype "passive"))
      (node (ref "DAC") (pin "7") (pinfunction "AVSS_7") (pintype "power_in"))
      (node (ref "IC1") (pin "1") (pinfunction "TEMP_1") (pintype "bidirectional"))
      (node (ref "IC1") (pin "3") (pinfunction "GND_3") (pintype "bidirectional"))
      (node (ref "IC2") (pin "1") (pinfunction "GND_1") (pintype "bidirectional"))
      (node (ref "IC3") (pin "1") (pinfunction "GND_1") (pintype "bidirectional"))
      (node (ref "JACK") (pin "1") (pinfunction "GND_1") (pintype "bidirectional"))
      (node (ref "OS1") (pin "E") (pinfunction "EMITTER_E") (pintype "passive"))
      (node (ref "OS2") (pin "E") (pinfunction "EMITTER_E") (pintype "passive"))
      (node (ref "OS3") (pin "E") (pinfunction "EMITTER_E") (pintype "passive"))
      (node (ref "OS4") (pin "E") (pinfunction "EMITTER_E") (pintype "passive"))
      (node (ref "OS5") (pin "E") (pinfunction "EMITTER_E") (pintype "passive"))
      (node (ref "OS6") (pin "E") (pinfunction "EMITTER_E") (pintype "passive"))
      (node (ref "OS7") (pin "E") (pinfunction "EMITTER_E") (pintype "passive"))
      (node (ref "OS8") (pin "E") (pinfunction "EMITTER_E") (pintype "passive"))
      (node (ref "P1") (pin "3") (pinfunction "GND_3") (pintype "bidirectional"))
      (node (ref "PROGRAM") (pin "1") (pinfunction "1_1") (pintype "passive"))
      (node (ref "PWR") (pin "2") (pinfunction "2_2") (pintype "passive"))
      (node (ref "R24") (pin "1") (pinfunction "1_1") (pintype "passive"))
      (node (ref "R28") (pin "1") (pinfunction "1_1") (pintype "passive"))
      (node (ref "R39") (pin "2") (pinfunction "2_2") (pintype "passive"))
      (node (ref "R41") (pin "2") (pinfunction "2_2") (pintype "passive"))
      (node (ref "U$1") (pin "1") (pinfunction "GND_1") (pintype "bidirectional"))
      (node (ref "U$14") (pin "-") (pinfunction "-_-") (pintype "passive"))
      (node (ref "U$18") (pin "A1") (pinfunction "P$1_A1") (pintype "bidirectional"))
      (node (ref "U$18") (pin "A2") (pinfunction "P$1_A2") (pintype "bidirectional"))
      (node (ref "U$19") (pin "A1") (pinfunction "P$1_A1") (pintype "bidirectional"))
      (node (ref "U$19") (pin "A2") (pinfunction "P$1_A2") (pintype "bidirectional"))
      (node (ref "U$2") (pin "1") (pinfunction "GND_1") (pintype "passive"))
      (node (ref "U$20") (pin "A1") (pinfunction "P$1_A1") (pintype "bidirectional"))
      (node (ref "U$20") (pin "A2") (pinfunction "P$1_A2") (pintype "bidirectional"))
      (node (ref "U$21") (pin "A1") (pinfunction "P$1_A1") (pintype "bidirectional"))
      (node (ref "U$21") (pin "A2") (pinfunction "P$1_A2") (pintype "bidirectional"))
      (node (ref "U$22") (pin "A1") (pinfunction "P$1_A1") (pintype "bidirectional"))
      (node (ref "U$22") (pin "A2") (pinfunction "P$1_A2") (pintype "bidirectional"))
      (node (ref "U$23") (pin "A1") (pinfunction "P$1_A1") (pintype "bidirectional"))
      (node (ref "U$23") (pin "A2") (pinfunction "P$1_A2") (pintype "bidirectional"))
      (node (ref "U$24") (pin "GND") (pinfunction "GND_GND") (pintype "bidirectional"))
      (node (ref "U$28") (pin "2") (pinfunction "E_2") (pintype "passive"))
      (node (ref "U$29") (pin "2") (pinfunction "E_2") (pintype "passive"))
      (node (ref "U$9") (pin "-") (pinfunction "-_-") (pintype "passive"))
      (node (ref "U1") (pin "6") (pinfunction "INH_6") (pintype "input"))
      (node (ref "U1") (pin "7") (pinfunction "VSS_7") (pintype "power_in"))
      (node (ref "U1") (pin "8") (pinfunction "VEE_8") (pintype "power_in"))
      (node (ref "U2") (pin "6") (pinfunction "INH_6") (pintype "input"))
      (node (ref "U2") (pin "7") (pinfunction "VSS_7") (pintype "power_in"))
      (node (ref "U2") (pin "8") (pinfunction "VEE_8") (pintype "power_in"))
      (node (ref "U3") (pin "1") (pinfunction "SHDN_1") (pintype "passive"))
      (node (ref "U3") (pin "7") (pinfunction "V-_7") (pintype "power_in"))
      (node (ref "UC1") (pin "23") (pinfunction "VSS_1_23") (pintype "power_in"))
      (node (ref "UC1") (pin "35") (pinfunction "VSS_2_35") (pintype "power_in"))
      (node (ref "UC1") (pin "47") (pinfunction "VSS_3_47") (pintype "power_in"))
      (node (ref "UC1") (pin "8") (pinfunction "VSS_A_8") (pintype "power_in"))
      (node (ref "X1") (pin "GND") (pinfunction "GND_GND") (pintype "bidirectional"))
    )
    (net (code "53") (name "Net-(BUT-1)") (class "Default")
      (node (ref "BUT") (pin "P$1") (pinfunction "1_P$1") (pintype "passive"))
      (node (ref "BUT") (pin "P$3") (pinfunction "3_P$3") (pintype "passive"))
      (node (ref "R38") (pin "2") (pinfunction "2_2") (pintype "passive"))
    )
    (net (code "54") (name "Net-(BUT-2)") (class "Default")
      (node (ref "BUT") (pin "P$2") (pinfunction "2_P$2") (pintype "passive"))
      (node (ref "BUT") (pin "P$4") (pinfunction "4_P$4") (pintype "passive"))
      (node (ref "R39") (pin "1") (pinfunction "1_1") (pintype "passive"))
      (node (ref "UC1") (pin "37") (pinfunction "PA14/JTCK/SWCLK_37") (pintype "bidirectional"))
      (node (ref "UC1") (pin "44") (pinfunction "BOOT0_44") (pintype "input"))
    )
    (net (code "55") (name "Net-(C14-+)") (class "Default")
      (node (ref "C14") (pin "A") (pinfunction "+_A") (pintype "passive"))
      (node (ref "D2") (pin "1") (pinfunction "C_1") (pintype "passive"))
      (node (ref "D3") (pin "1") (pinfunction "C_1") (pintype "passive"))
      (node (ref "IC2") (pin "3") (pinfunction "VIN_3") (pintype "bidirectional"))
      (node (ref "IC3") (pin "3") (pinfunction "VIN_3") (pintype "bidirectional"))
    )
    (net (code "56") (name "Net-(C17-Pad2)") (class "Default")
      (node (ref "C17") (pin "2") (pinfunction "2_2") (pintype "passive"))
      (node (ref "R22") (pin "1") (pinfunction "1_1") (pintype "passive"))
    )
    (net (code "57") (name "Net-(D1-PadA)") (class "Default")
      (node (ref "D1") (pin "A") (pinfunction "A_A") (pintype "passive"))
      (node (ref "R30") (pin "2") (pinfunction "2_2") (pintype "passive"))
    )
    (net (code "58") (name "Net-(D4-PadA)") (class "Default")
      (node (ref "D4") (pin "A") (pinfunction "A_A") (pintype "passive"))
      (node (ref "R26") (pin "2") (pinfunction "2_2") (pintype "passive"))
    )
    (net (code "59") (name "Net-(D5-PadA)") (class "Default")
      (node (ref "D5") (pin "A") (pinfunction "A_A") (pintype "passive"))
      (node (ref "R27") (pin "2") (pinfunction "2_2") (pintype "passive"))
    )
    (net (code "60") (name "Net-(IC1-CHRG)") (class "Default")
      (node (ref "D4") (pin "C") (pinfunction "C_C") (pintype "passive"))
      (node (ref "IC1") (pin "7") (pinfunction "CHRG_7") (pintype "bidirectional"))
    )
    (net (code "61") (name "Net-(IC1-PROG)") (class "Default")
      (node (ref "IC1") (pin "2") (pinfunction "PROG_2") (pintype "bidirectional"))
      (node (ref "R24") (pin "2") (pinfunction "2_2") (pintype "passive"))
    )
    (net (code "62") (name "Net-(IC1-STDBY)") (class "Default")
      (node (ref "D5") (pin "C") (pinfunction "C_C") (pintype "passive"))
      (node (ref "IC1") (pin "6") (pinfunction "STDBY_6") (pintype "bidirectional"))
    )
    (net (code "63") (name "Net-(JACK-IN_A)") (class "Default")
      (node (ref "JACK") (pin "2") (pinfunction "IN_A_2") (pintype "bidirectional"))
      (node (ref "JACK") (pin "5") (pinfunction "IN_B_5") (pintype "bidirectional"))
      (node (ref "R19") (pin "2") (pinfunction "2_2") (pintype "passive"))
    )
    (net (code "64") (name "Net-(OS1-ANODE)") (class "Default")
      (node (ref "OS1") (pin "A") (pinfunction "ANODE_A") (pintype "passive"))
      (node (ref "R3") (pin "2") (pinfunction "2_2") (pintype "passive"))
    )
    (net (code "65") (name "Net-(OS2-ANODE)") (class "Default")
      (node (ref "OS2") (pin "A") (pinfunction "ANODE_A") (pintype "passive"))
      (node (ref "R7") (pin "1") (pinfunction "1_1") (pintype "passive"))
    )
    (net (code "66") (name "Net-(OS3-ANODE)") (class "Default")
      (node (ref "OS3") (pin "A") (pinfunction "ANODE_A") (pintype "passive"))
      (node (ref "R10") (pin "1") (pinfunction "1_1") (pintype "passive"))
    )
    (net (code "67") (name "Net-(OS4-ANODE)") (class "Default")
      (node (ref "OS4") (pin "A") (pinfunction "ANODE_A") (pintype "passive"))
      (node (ref "R11") (pin "1") (pinfunction "1_1") (pintype "passive"))
    )
    (net (code "68") (name "Net-(OS5-ANODE)") (class "Default")
      (node (ref "OS5") (pin "A") (pinfunction "ANODE_A") (pintype "passive"))
      (node (ref "R5") (pin "2") (pinfunction "2_2") (pintype "passive"))
    )
    (net (code "69") (name "Net-(OS6-ANODE)") (class "Default")
      (node (ref "OS6") (pin "A") (pinfunction "ANODE_A") (pintype "passive"))
      (node (ref "R8") (pin "1") (pinfunction "1_1") (pintype "passive"))
    )
    (net (code "70") (name "Net-(OS7-ANODE)") (class "Default")
      (node (ref "OS7") (pin "A") (pinfunction "ANODE_A") (pintype "passive"))
      (node (ref "R9") (pin "1") (pinfunction "1_1") (pintype "passive"))
    )
    (net (code "71") (name "Net-(OS8-ANODE)") (class "Default")
      (node (ref "OS8") (pin "A") (pinfunction "ANODE_A") (pintype "passive"))
      (node (ref "R12") (pin "1") (pinfunction "1_1") (pintype "passive"))
    )
    (net (code "72") (name "Net-(R31-Pad1)") (class "Default")
      (node (ref "R31") (pin "1") (pinfunction "1_1") (pintype "passive"))
      (node (ref "X1") (pin "D-") (pinfunction "D-_D-") (pintype "bidirectional"))
    )
    (net (code "73") (name "Net-(R32-Pad1)") (class "Default")
      (node (ref "R32") (pin "1") (pinfunction "1_1") (pintype "passive"))
      (node (ref "X1") (pin "D+") (pinfunction "D+_D+") (pintype "bidirectional"))
    )
    (net (code "74") (name "Net-(RESET-1)") (class "Default")
      (node (ref "R41") (pin "1") (pinfunction "1_1") (pintype "passive"))
      (node (ref "RESET") (pin "P$1") (pinfunction "1_P$1") (pintype "passive"))
      (node (ref "RESET") (pin "P$3") (pinfunction "3_P$3") (pintype "passive"))
    )
    (net (code "75") (name "Net-(U$1-C+)") (class "Default")
      (node (ref "C15") (pin "2") (pinfunction "2_2") (pintype "passive"))
      (node (ref "U$1") (pin "5") (pinfunction "C+_5") (pintype "bidirectional"))
    )
    (net (code "76") (name "Net-(U$1-C-)") (class "Default")
      (node (ref "C15") (pin "1") (pinfunction "1_1") (pintype "passive"))
      (node (ref "U$1") (pin "3") (pinfunction "C-_3") (pintype "bidirectional"))
    )
    (net (code "77") (name "Net-(U$1-VOUT)") (class "Default")
      (node (ref "C16") (pin "2") (pinfunction "2_2") (pintype "passive"))
      (node (ref "U$1") (pin "2") (pinfunction "VOUT_2") (pintype "bidirectional"))
      (node (ref "U$2") (pin "3") (pinfunction "VIN_3") (pintype "input"))
    )
    (net (code "78") (name "Net-(U$28-B)") (class "Default")
      (node (ref "R1") (pin "2") (pinfunction "2_2") (pintype "passive"))
      (node (ref "U$28") (pin "1") (pinfunction "B_1") (pintype "passive"))
    )
    (net (code "79") (name "Net-(U$29-B)") (class "Default")
      (node (ref "R2") (pin "2") (pinfunction "2_2") (pintype "passive"))
      (node (ref "U$29") (pin "1") (pinfunction "B_1") (pintype "passive"))
    )
    (net (code "80") (name "Net-(U3-BYPASS)") (class "Default")
      (node (ref "C1") (pin "2") (pinfunction "2_2") (pintype "passive"))
      (node (ref "U3") (pin "2") (pinfunction "BYPASS_2") (pintype "passive"))
      (node (ref "U3") (pin "3") (pinfunction "IN+_3") (pintype "input"))
    )
    (net (code "81") (name "Net-(U3-IN-)") (class "Default")
      (node (ref "R21") (pin "1") (pinfunction "1_1") (pintype "passive"))
      (node (ref "R22") (pin "2") (pinfunction "2_2") (pintype "passive"))
      (node (ref "U3") (pin "4") (pinfunction "IN-_4") (pintype "input"))
    )
    (net (code "82") (name "Net-(U3-VOUTB)") (class "Default")
      (node (ref "SPEAKER") (pin "2") (pinfunction "2_2") (pintype "passive"))
      (node (ref "U3") (pin "8") (pinfunction "VOUTB_8") (pintype "output"))
    )
    (net (code "83") (name "Net-(UC1-PA13{slash}JTMS{slash}SWDIO)") (class "Default")
      (node (ref "R30") (pin "1") (pinfunction "1_1") (pintype "passive"))
      (node (ref "UC1") (pin "34") (pinfunction "PA13/JTMS/SWDIO_34") (pintype "bidirectional"))
    )
    (net (code "84") (name "unconnected-(DAC-~{SHDN}-Pad6)") (class "Default")
      (node (ref "DAC") (pin "6") (pinfunction "~{SHDN}_6") (pintype "input"))
    )
    (net (code "85") (name "unconnected-(U1-7-Pad4)") (class "Default")
      (node (ref "U1") (pin "4") (pinfunction "7_4") (pintype "bidirectional"))
    )
    (net (code "86") (name "unconnected-(U2-7-Pad4)") (class "Default")
      (node (ref "U2") (pin "4") (pinfunction "7_4") (pintype "bidirectional"))
    )
    (net (code "87") (name "unconnected-(UC1-PA3{slash}USART2_RX{slash}ADC12_IN3{slash}TIM2_CH4-Pad13)") (class "Default")
      (node (ref "UC1") (pin "13") (pinfunction "PA3/USART2_RX/ADC12_IN3/TIM2_CH4_13") (pintype "bidirectional"))
    )
    (net (code "88") (name "unconnected-(UC1-PA4{slash}SPI1_NSS{slash}USART2_CK{slash}ADC12_IN4-Pad14)") (class "Default")
      (node (ref "UC1") (pin "14") (pinfunction "PA4/SPI1_NSS/USART2_CK/ADC12_IN4_14") (pintype "bidirectional"))
    )
    (net (code "89") (name "unconnected-(UC1-PA5{slash}SPI1_SCK{slash}ADC12_IN5-Pad15)") (class "Default")
      (node (ref "UC1") (pin "15") (pinfunction "PA5/SPI1_SCK/ADC12_IN5_15") (pintype "bidirectional"))
    )
    (net (code "90") (name "unconnected-(UC1-PA6{slash}SPI1_MISO{slash}ADC12_IN6{slash}TIM3_CH1-Pad16)") (class "Default")
      (node (ref "UC1") (pin "16") (pinfunction "PA6/SPI1_MISO/ADC12_IN6/TIM3_CH1_16") (pintype "bidirectional"))
    )
    (net (code "91") (name "unconnected-(UC1-PA7{slash}SPI1_MOSI{slash}ADC12_IN7{slash}TIM3_CH2-Pad17)") (class "Default")
      (node (ref "UC1") (pin "17") (pinfunction "PA7/SPI1_MOSI/ADC12_IN7/TIM3_CH2_17") (pintype "bidirectional"))
    )
    (net (code "92") (name "unconnected-(UC1-PA15{slash}JTDI-Pad38)") (class "Default")
      (node (ref "UC1") (pin "38") (pinfunction "PA15/JTDI_38") (pintype "bidirectional"))
    )
    (net (code "93") (name "unconnected-(UC1-PB0{slash}ADC12_IN8{slash}TIM3_CH3-Pad18)") (class "Default")
      (node (ref "UC1") (pin "18") (pinfunction "PB0/ADC12_IN8/TIM3_CH3_18") (pintype "bidirectional"))
    )
    (net (code "94") (name "unconnected-(UC1-PB1{slash}ADC12_IN9{slash}TIM3_CH4-Pad19)") (class "Default")
      (node (ref "UC1") (pin "19") (pinfunction "PB1/ADC12_IN9/TIM3_CH4_19") (pintype "bidirectional"))
    )
    (net (code "95") (name "unconnected-(UC1-PB3{slash}JTDO-Pad39)") (class "Default")
      (node (ref "UC1") (pin "39") (pinfunction "PB3/JTDO_39") (pintype "bidirectional"))
    )
    (net (code "96") (name "unconnected-(UC1-PB4{slash}NJTRST-Pad40)") (class "Default")
      (node (ref "UC1") (pin "40") (pinfunction "PB4/NJTRST_40") (pintype "bidirectional"))
    )
    (net (code "97") (name "unconnected-(UC1-PB14{slash}SPI2_MISO{slash}USART3_RTS{slash}TIM1_CH2N-Pad27)") (class "Default")
      (node (ref "UC1") (pin "27") (pinfunction "PB14/SPI2_MISO/USART3_RTS/TIM1_CH2N_27") (pintype "input"))
    )
    (net (code "98") (name "unconnected-(UC1-PC13-TAMPER-RTC-Pad2)") (class "Default")
      (node (ref "UC1") (pin "2") (pinfunction "PC13-TAMPER-RTC_2") (pintype "input"))
    )
  )
)
